# NNLightSwitcher_charge.net
KiCad netlist of a schematic drawn in Altium Designer
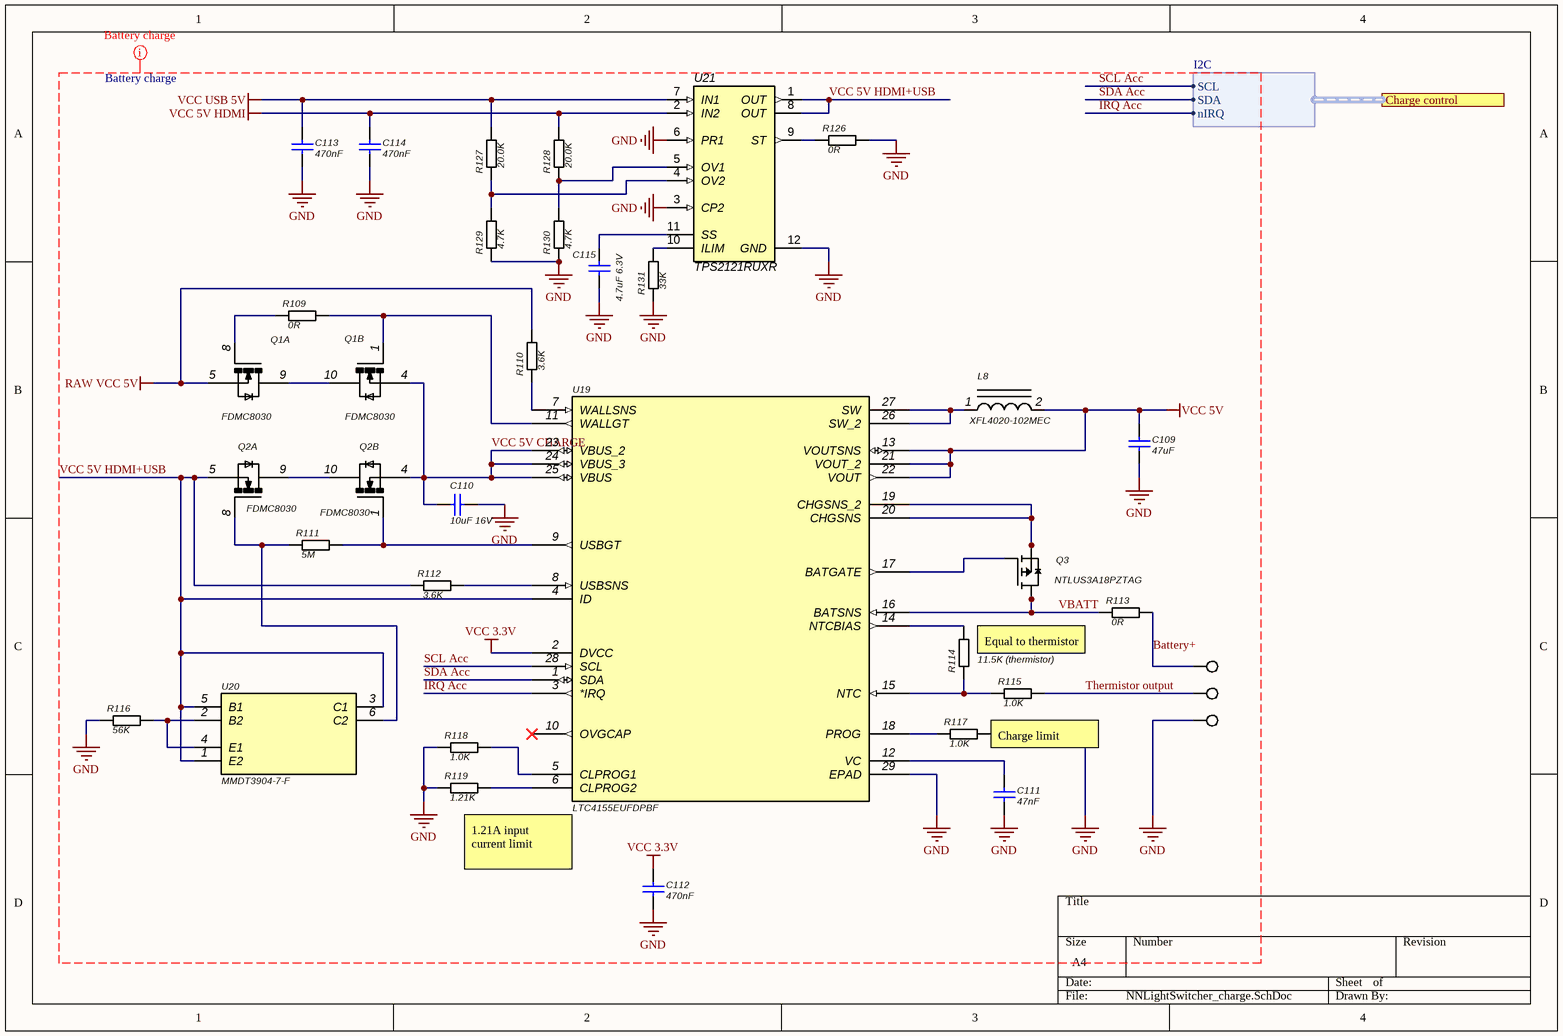
[diagram p0: NNLightSwitcher_charge.SchDoc]

(export (version "E")
  (design (tool "Eeschema 10.0.6"))
  (components
    (comp (ref "C109")
      (value "47uF")
      (footprint "Res_0805")
      (libsource (lib "NNLightSwitcher") (part "Capacitor 47uF"))
    )
    (comp (ref "C110")
      (value "10uF 16V")
      (footprint "*0603")
      (description "EMK107BBJ106MA-T")
      (fields (field (name "TOLERANCE") "20%"))
      (libsource (lib "NNLightSwitcher") (part "Capacitor 10uF 16V"))
    )
    (comp (ref "C111")
      (value "47nF")
      (footprint "0402")
      (libsource (lib "NNLightSwitcher") (part "Capacitor 47nF"))
    )
    (comp (ref "C112")
      (value "470nF")
      (footprint "0402")
      (libsource (lib "NNLightSwitcher") (part "Capacitor 470nF"))
    )
    (comp (ref "C113")
      (value "470nF")
      (footprint "0402")
      (libsource (lib "NNLightSwitcher") (part "Capacitor 470nF"))
    )
    (comp (ref "C114")
      (value "470nF")
      (footprint "0402")
      (libsource (lib "NNLightSwitcher") (part "Capacitor 470nF"))
    )
    (comp (ref "C115")
      (value "4.7uF 6.3V")
      (footprint "*0603")
      (libsource (lib "NNLightSwitcher") (part "Capacitor 4.7uF 6.3V"))
    )
    (comp (ref "L8")
      (value "XFL4020-102MEC")
      (footprint "*INDM4040X210")
      (description "Power inductor, shielded, 20% tol, SMT, RoHS, halogen free")
      (fields (field (name "TOLERANCE") "20%"))
      (libsource (lib "NNLightSwitcher") (part "XFL4020-102MEC"))
    )
    (comp (ref "Q1")
      (value "FDMC8030")
      (footprint "*TRANS_FDMC8030")
      (description "Mosfet Array 2 N-Channel (Dual) 40V 12A 800mW Surface Mount 8-Power33 (3x3)")
      (libsource (lib "NNLightSwitcher") (part "FDMC8030"))
    )
    (comp (ref "Q2")
      (value "FDMC8030")
      (footprint "*TRANS_FDMC8030")
      (description "Mosfet Array 2 N-Channel (Dual) 40V 12A 800mW Surface Mount 8-Power33 (3x3)")
      (libsource (lib "NNLightSwitcher") (part "FDMC8030"))
    )
    (comp (ref "Q3")
      (value "NTLUS3A18PZTAG")
      (footprint "*TRANS_NTLUS3A18PZTAG")
      (description "Power MOSFET -20V -8.2A 18 mOhm Single P-Channel UDFN6 with ESD Protection")
      (libsource (lib "NNLightSwitcher") (part "NTLUS3A18PZTAG"))
    )
    (comp (ref "R109")
      (value "0R")
      (footprint "0402")
      (libsource (lib "NNLightSwitcher") (part "Resistor 0R"))
    )
    (comp (ref "R110")
      (value "3.6K")
      (footprint "0402")
      (libsource (lib "NNLightSwitcher") (part "Resistor 3.6K"))
    )
    (comp (ref "R111")
      (value "5M")
      (footprint "0402")
      (libsource (lib "NNLightSwitcher") (part "Resistor 0R"))
    )
    (comp (ref "R112")
      (value "3.6K")
      (footprint "0402")
      (libsource (lib "NNLightSwitcher") (part "Resistor 3.6K"))
    )
    (comp (ref "R113")
      (value "0R")
      (footprint "0402")
      (libsource (lib "NNLightSwitcher") (part "Resistor 0R"))
    )
    (comp (ref "R114")
      (value "11.5K (thermistor)")
      (footprint "0402")
      (libsource (lib "NNLightSwitcher") (part "Resistor 11.5K"))
    )
    (comp (ref "R115")
      (value "1.0K")
      (footprint "0402")
      (libsource (lib "NNLightSwitcher") (part "Resistor 1.0K"))
    )
    (comp (ref "R116")
      (value "56K")
      (footprint "0402")
      (libsource (lib "NNLightSwitcher") (part "Resistor 56K"))
    )
    (comp (ref "R117")
      (value "1.0K")
      (footprint "0402")
      (libsource (lib "NNLightSwitcher") (part "Resistor 1.0K"))
    )
    (comp (ref "R118")
      (value "1.0K")
      (footprint "0402")
      (libsource (lib "NNLightSwitcher") (part "Resistor 1.0K"))
    )
    (comp (ref "R119")
      (value "1.21K")
      (footprint "0402")
      (libsource (lib "NNLightSwitcher") (part "Resistor 1.21K"))
    )
    (comp (ref "R126")
      (value "0R")
      (footprint "0402")
      (libsource (lib "NNLightSwitcher") (part "Resistor 0R"))
    )
    (comp (ref "R127")
      (value "20.0K")
      (footprint "0402")
      (libsource (lib "NNLightSwitcher") (part "Resistor 20.0K"))
    )
    (comp (ref "R128")
      (value "20.0K")
      (footprint "0402")
      (libsource (lib "NNLightSwitcher") (part "Resistor 20.0K"))
    )
    (comp (ref "R129")
      (value "4.7K")
      (footprint "0402")
      (libsource (lib "NNLightSwitcher") (part "Resistor 4.7K"))
    )
    (comp (ref "R130")
      (value "4.7K")
      (footprint "0402")
      (libsource (lib "NNLightSwitcher") (part "Resistor 4.7K"))
    )
    (comp (ref "R131")
      (value "33K")
      (footprint "0402")
      (libsource (lib "NNLightSwitcher") (part "Resistor 33K"))
    )
    (comp (ref "TP60")
      (value "Test point")
      (footprint "Connection")
      (description "Test Point, Miniature, SMT")
      (libsource (lib "NNLightSwitcher") (part "Test point"))
    )
    (comp (ref "TP61")
      (value "Test point")
      (footprint "Connection")
      (description "Test Point, Miniature, SMT")
      (libsource (lib "NNLightSwitcher") (part "Test point"))
    )
    (comp (ref "TP62")
      (value "Test point")
      (footprint "Connection")
      (description "Test Point, Miniature, SMT")
      (libsource (lib "NNLightSwitcher") (part "Test point"))
    )
    (comp (ref "U19")
      (value "LTC4155EUFDPBF")
      (footprint "*QFN-28_UFD")
      (description "LTC4155 - Dual Input Power Manager/ 3.5A Li-Ion Battery Charger with I2C Control and USB OTG")
      (libsource (lib "NNLightSwitcher") (part "LTC4155EUFDPBF"))
    )
    (comp (ref "U20")
      (value "MMDT3904-7-F")
      (footprint "*SOT65P210X110-6N")
      (description "TRANSISTOR, ARRAY, DUAL NPN, 40V, 200mA, SOT-363-6, FULL REEL")
      (libsource (lib "NNLightSwitcher") (part "MMDT3904-7-F"))
    )
    (comp (ref "U21")
      (value "TPS2121RUXR")
      (footprint "*IC_TPS2121RUXR_TPS2121RUXR(Primary)")
      (description "PWR MGMT BATTERY MGMT")
      (fields (field (name "MF") "Texas Instruments"))
      (libsource (lib "NNLightSwitcher") (part "TPS2121RUXR"))
    )
  )
  (nets
    (net (code "2") (name "/Battery+") (class "Default")
      (node (ref "R113") (pin "2") (pinfunction "2_2") (pintype "passive"))
      (node (ref "TP60") (pin "1") (pintype "passive"))
    )
    (net (code "3") (name "/IRQ Acc") (class "Default")
      (node (ref "U19") (pin "3") (pinfunction "*IRQ_3") (pintype "output"))
    )
    (net (code "4") (name "/SCL Acc") (class "Default")
      (node (ref "U19") (pin "28") (pinfunction "SCL_28") (pintype "input"))
    )
    (net (code "5") (name "/SDA Acc") (class "Default")
      (node (ref "U19") (pin "1") (pinfunction "SDA_1") (pintype "bidirectional"))
    )
    (net (code "6") (name "/Thermistor output") (class "Default")
      (node (ref "R115") (pin "2") (pinfunction "2_2") (pintype "passive"))
      (node (ref "TP61") (pin "1") (pintype "passive"))
    )
    (net (code "7") (name "/VBATT") (class "Default")
      (node (ref "Q3") (pin "1") (pinfunction "D_1") (pintype "passive"))
      (node (ref "Q3") (pin "2") (pinfunction "D_2") (pintype "passive"))
      (node (ref "Q3") (pin "5") (pinfunction "D_5") (pintype "passive"))
      (node (ref "Q3") (pin "6") (pinfunction "D_6") (pintype "passive"))
      (node (ref "Q3") (pin "7") (pinfunction "D_7") (pintype "passive"))
      (node (ref "R113") (pin "1") (pinfunction "1_1") (pintype "passive"))
      (node (ref "U19") (pin "16") (pinfunction "BATSNS_16") (pintype "input"))
    )
    (net (code "8") (name "/VCC 5V CHARGE") (class "Default")
      (node (ref "C110") (pin "2") (pinfunction "2_2") (pintype "passive"))
      (node (ref "Q1") (pin "4") (pinfunction "S1_4") (pintype "passive"))
      (node (ref "Q2") (pin "4") (pinfunction "S1_4") (pintype "passive"))
      (node (ref "U19") (pin "23") (pinfunction "VBUS_2_23") (pintype "bidirectional"))
      (node (ref "U19") (pin "24") (pinfunction "VBUS_3_24") (pintype "bidirectional"))
      (node (ref "U19") (pin "25") (pinfunction "VBUS_25") (pintype "bidirectional"))
    )
    (net (code "9") (name "/VCC 5V HDMI+USB") (class "Default")
      (node (ref "Q2") (pin "5") (pinfunction "S2_5") (pintype "passive"))
      (node (ref "R112") (pin "1") (pinfunction "1_1") (pintype "passive"))
      (node (ref "U19") (pin "4") (pinfunction "ID_4") (pintype "passive"))
      (node (ref "U20") (pin "1") (pinfunction "E2_1") (pintype "passive"))
      (node (ref "U20") (pin "3") (pinfunction "C1_3") (pintype "passive"))
      (node (ref "U20") (pin "5") (pinfunction "B1_5") (pintype "passive"))
      (node (ref "U21") (pin "1") (pinfunction "OUT_1") (pintype "output"))
      (node (ref "U21") (pin "8") (pinfunction "OUT_8") (pintype "passive"))
    )
    (net (code "11") (name "GND") (class "Default")
      (node (ref "C109") (pin "2") (pinfunction "2_2") (pintype "passive"))
      (node (ref "C110") (pin "1") (pinfunction "1_1") (pintype "passive"))
      (node (ref "C111") (pin "2") (pinfunction "2_2") (pintype "passive"))
      (node (ref "C112") (pin "2") (pinfunction "2_2") (pintype "passive"))
      (node (ref "C113") (pin "2") (pinfunction "2_2") (pintype "passive"))
      (node (ref "C114") (pin "2") (pinfunction "2_2") (pintype "passive"))
      (node (ref "C115") (pin "2") (pinfunction "2_2") (pintype "passive"))
      (node (ref "R116") (pin "1") (pinfunction "1_1") (pintype "passive"))
      (node (ref "R117") (pin "2") (pinfunction "2_2") (pintype "passive"))
      (node (ref "R118") (pin "1") (pinfunction "1_1") (pintype "passive"))
      (node (ref "R119") (pin "1") (pinfunction "1_1") (pintype "passive"))
      (node (ref "R126") (pin "2") (pinfunction "2_2") (pintype "passive"))
      (node (ref "R129") (pin "1") (pinfunction "1_1") (pintype "passive"))
      (node (ref "R130") (pin "1") (pinfunction "1_1") (pintype "passive"))
      (node (ref "R131") (pin "1") (pinfunction "1_1") (pintype "passive"))
      (node (ref "TP62") (pin "1") (pintype "passive"))
      (node (ref "U19") (pin "29") (pinfunction "EPAD_29") (pintype "passive"))
      (node (ref "U21") (pin "12") (pinfunction "GND_12") (pintype "power_in"))
      (node (ref "U21") (pin "3") (pinfunction "CP2_3") (pintype "input"))
      (node (ref "U21") (pin "6") (pinfunction "PR1_6") (pintype "input"))
    )
    (net (code "12") (name "Net-(Q1A-D2)") (class "Default")
      (node (ref "Q1") (pin "10") (pinfunction "D1_10") (pintype "passive"))
      (node (ref "Q1") (pin "9") (pinfunction "D2_9") (pintype "passive"))
    )
    (net (code "13") (name "Net-(Q1A-G2)") (class "Default")
      (node (ref "Q1") (pin "8") (pinfunction "G2_8") (pintype "passive"))
      (node (ref "R109") (pin "1") (pinfunction "1_1") (pintype "passive"))
    )
    (net (code "14") (name "Net-(Q1B-G1)") (class "Default")
      (node (ref "Q1") (pin "1") (pinfunction "G1_1") (pintype "passive"))
      (node (ref "R109") (pin "2") (pinfunction "2_2") (pintype "passive"))
      (node (ref "U19") (pin "11") (pinfunction "WALLGT_11") (pintype "output"))
    )
    (net (code "15") (name "Net-(Q2A-D2)") (class "Default")
      (node (ref "Q2") (pin "10") (pinfunction "D1_10") (pintype "passive"))
      (node (ref "Q2") (pin "9") (pinfunction "D2_9") (pintype "passive"))
    )
    (net (code "16") (name "Net-(Q2A-G2)") (class "Default")
      (node (ref "Q2") (pin "8") (pinfunction "G2_8") (pintype "passive"))
      (node (ref "R111") (pin "1") (pinfunction "1_1") (pintype "passive"))
      (node (ref "U20") (pin "6") (pinfunction "C2_6") (pintype "passive"))
    )
    (net (code "17") (name "Net-(Q2B-G1)") (class "Default")
      (node (ref "Q2") (pin "1") (pinfunction "G1_1") (pintype "passive"))
      (node (ref "R111") (pin "2") (pinfunction "2_2") (pintype "passive"))
      (node (ref "U19") (pin "9") (pinfunction "USBGT_9") (pintype "output"))
    )
    (net (code "18") (name "Net-(Q3-G)") (class "Default")
      (node (ref "Q3") (pin "3") (pinfunction "G_3") (pintype "passive"))
      (node (ref "U19") (pin "17") (pinfunction "BATGATE_17") (pintype "output"))
    )
    (net (code "19") (name "Net-(U19-CHGSNS)") (class "Default")
      (node (ref "Q3") (pin "4") (pinfunction "S_4") (pintype "passive"))
      (node (ref "Q3") (pin "8") (pinfunction "S_8") (pintype "passive"))
      (node (ref "U19") (pin "19") (pinfunction "CHGSNS_2_19") (pintype "passive"))
      (node (ref "U19") (pin "20") (pinfunction "CHGSNS_20") (pintype "passive"))
    )
    (net (code "20") (name "Net-(U19-CLPROG1)") (class "Default")
      (node (ref "R118") (pin "2") (pinfunction "2_2") (pintype "passive"))
      (node (ref "U19") (pin "5") (pinfunction "CLPROG1_5") (pintype "passive"))
    )
    (net (code "21") (name "Net-(U19-CLPROG2)") (class "Default")
      (node (ref "R119") (pin "2") (pinfunction "2_2") (pintype "passive"))
      (node (ref "U19") (pin "6") (pinfunction "CLPROG2_6") (pintype "passive"))
    )
    (net (code "22") (name "Net-(U19-NTC)") (class "Default")
      (node (ref "R114") (pin "1") (pinfunction "1_1") (pintype "passive"))
      (node (ref "R115") (pin "1") (pinfunction "1_1") (pintype "passive"))
      (node (ref "U19") (pin "15") (pinfunction "NTC_15") (pintype "input"))
    )
    (net (code "23") (name "Net-(U19-NTCBIAS)") (class "Default")
      (node (ref "R114") (pin "2") (pinfunction "2_2") (pintype "passive"))
      (node (ref "U19") (pin "14") (pinfunction "NTCBIAS_14") (pintype "output"))
    )
    (net (code "24") (name "Net-(U19-PROG)") (class "Default")
      (node (ref "R117") (pin "1") (pinfunction "1_1") (pintype "passive"))
      (node (ref "U19") (pin "18") (pinfunction "PROG_18") (pintype "passive"))
    )
    (net (code "25") (name "Net-(U19-SW)") (class "Default")
      (node (ref "L8") (pin "1") (pinfunction "1_1") (pintype "passive"))
      (node (ref "U19") (pin "26") (pinfunction "SW_2_26") (pintype "passive"))
      (node (ref "U19") (pin "27") (pinfunction "SW_27") (pintype "passive"))
    )
    (net (code "26") (name "Net-(U19-USBSNS)") (class "Default")
      (node (ref "R112") (pin "2") (pinfunction "2_2") (pintype "passive"))
      (node (ref "U19") (pin "8") (pinfunction "USBSNS_8") (pintype "input"))
    )
    (net (code "27") (name "Net-(U19-VC)") (class "Default")
      (node (ref "C111") (pin "1") (pinfunction "1_1") (pintype "passive"))
      (node (ref "U19") (pin "12") (pinfunction "VC_12") (pintype "passive"))
    )
    (net (code "28") (name "Net-(U19-WALLSNS)") (class "Default")
      (node (ref "R110") (pin "1") (pinfunction "1_1") (pintype "passive"))
      (node (ref "U19") (pin "7") (pinfunction "WALLSNS_7") (pintype "input"))
    )
    (net (code "29") (name "Net-(U20-B2)") (class "Default")
      (node (ref "R116") (pin "2") (pinfunction "2_2") (pintype "passive"))
      (node (ref "U20") (pin "2") (pinfunction "B2_2") (pintype "passive"))
      (node (ref "U20") (pin "4") (pinfunction "E1_4") (pintype "passive"))
    )
    (net (code "30") (name "Net-(U21-ILIM)") (class "Default")
      (node (ref "R131") (pin "2") (pinfunction "2_2") (pintype "passive"))
      (node (ref "U21") (pin "10") (pinfunction "ILIM_10") (pintype "passive"))
    )
    (net (code "31") (name "Net-(U21-OV1)") (class "Default")
      (node (ref "R128") (pin "1") (pinfunction "1_1") (pintype "passive"))
      (node (ref "R130") (pin "2") (pinfunction "2_2") (pintype "passive"))
      (node (ref "U21") (pin "5") (pinfunction "OV1_5") (pintype "input"))
    )
    (net (code "32") (name "Net-(U21-OV2)") (class "Default")
      (node (ref "R127") (pin "1") (pinfunction "1_1") (pintype "passive"))
      (node (ref "R129") (pin "2") (pinfunction "2_2") (pintype "passive"))
      (node (ref "U21") (pin "4") (pinfunction "OV2_4") (pintype "input"))
    )
    (net (code "33") (name "Net-(U21-SS)") (class "Default")
      (node (ref "C115") (pin "1") (pinfunction "1_1") (pintype "passive"))
      (node (ref "U21") (pin "11") (pinfunction "SS_11") (pintype "passive"))
    )
    (net (code "34") (name "Net-(U21-ST)") (class "Default")
      (node (ref "R126") (pin "1") (pinfunction "1_1") (pintype "passive"))
      (node (ref "U21") (pin "9") (pinfunction "ST_9") (pintype "output"))
    )
    (net (code "35") (name "RAW VCC 5V") (class "Default")
      (node (ref "Q1") (pin "5") (pinfunction "S2_5") (pintype "passive"))
      (node (ref "R110") (pin "2") (pinfunction "2_2") (pintype "passive"))
    )
    (net (code "36") (name "VCC 3.3V") (class "Default")
      (node (ref "C112") (pin "1") (pinfunction "1_1") (pintype "passive"))
      (node (ref "U19") (pin "2") (pinfunction "DVCC_2") (pintype "power_in"))
    )
    (net (code "37") (name "VCC 5V") (class "Default")
      (node (ref "C109") (pin "1") (pinfunction "1_1") (pintype "passive"))
      (node (ref "L8") (pin "2") (pinfunction "2_2") (pintype "passive"))
      (node (ref "U19") (pin "13") (pinfunction "VOUTSNS_13") (pintype "bidirectional"))
      (node (ref "U19") (pin "21") (pinfunction "VOUT_2_21") (pintype "passive"))
      (node (ref "U19") (pin "22") (pinfunction "VOUT_22") (pintype "output"))
    )
    (net (code "38") (name "VCC 5V HDMI") (class "Default")
      (node (ref "C114") (pin "1") (pinfunction "1_1") (pintype "passive"))
      (node (ref "R128") (pin "2") (pinfunction "2_2") (pintype "passive"))
      (node (ref "U21") (pin "2") (pinfunction "IN2_2") (pintype "input"))
    )
    (net (code "39") (name "VCC USB 5V") (class "Default")
      (node (ref "C113") (pin "1") (pinfunction "1_1") (pintype "passive"))
      (node (ref "R127") (pin "2") (pinfunction "2_2") (pintype "passive"))
      (node (ref "U21") (pin "7") (pinfunction "IN1_7") (pintype "input"))
    )
    (net (code "40") (name "unconnected-(U19-OVGCAP-Pad10)") (class "Default")
      (node (ref "U19") (pin "10") (pinfunction "OVGCAP_10") (pintype "output+no_connect"))
    )
  )
)
